# lp_pic32_s.net
KiCad netlist of a schematic drawn in EAGLE
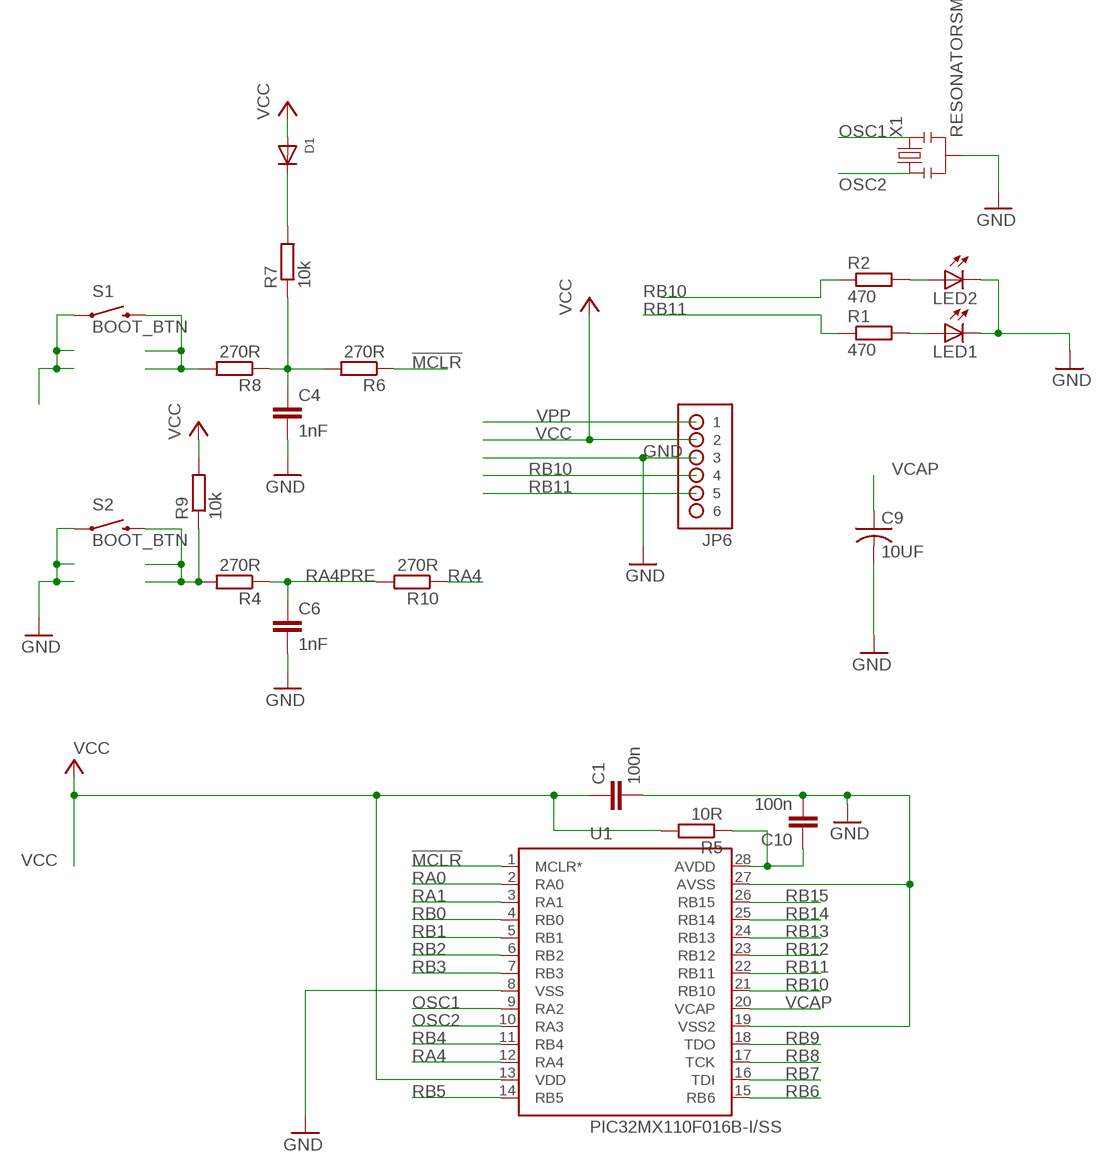
[diagram p0: schematic, sheet 1]

(export (version "E")
  (design (tool "Eeschema 10.0.6"))
  (components
    (comp (ref "C1")
      (value "100n")
      (footprint "eagle-import:C0805")
      (libsource (lib "eagle-import") (part "C-EUC0805"))
    )
    (comp (ref "C4")
      (value "1nF")
      (footprint "eagle-import:C0805")
      (libsource (lib "eagle-import") (part "resistor_C-EUC0805"))
    )
    (comp (ref "C6")
      (value "1nF")
      (footprint "eagle-import:C0805")
      (libsource (lib "eagle-import") (part "resistor_C-EUC0805"))
    )
    (comp (ref "C9")
      (value "10UF")
      (footprint "eagle-import:C1206")
      (libsource (lib "eagle-import") (part "C-USC1206"))
    )
    (comp (ref "C10")
      (value "100n")
      (footprint "eagle-import:C0805")
      (libsource (lib "eagle-import") (part "C-EUC0805"))
    )
    (comp (ref "D1")
      (value "DIODESOD-323F")
      (footprint "eagle-import:SOD-323F")
      (libsource (lib "eagle-import") (part "DIODESOD-323F"))
    )
    (comp (ref "JP6")
      (value "No Load")
      (footprint "eagle-import:HDR-1X6_OFFSET")
      (libsource (lib "eagle-import") (part "HDR-1X6-OFFSET"))
    )
    (comp (ref "LED1")
      (value "0")
      (footprint "eagle-import:CHIPLED_1206")
      (libsource (lib "eagle-import") (part "LEDCHIPLED_1206"))
    )
    (comp (ref "LED2")
      (value "0")
      (footprint "eagle-import:CHIPLED_1206")
      (libsource (lib "eagle-import") (part "LEDCHIPLED_1206"))
    )
    (comp (ref "R1")
      (value "470")
      (footprint "eagle-import:R0805")
      (libsource (lib "eagle-import") (part "R-EU_R0805"))
    )
    (comp (ref "R2")
      (value "470")
      (footprint "eagle-import:R0805")
      (libsource (lib "eagle-import") (part "R-EU_R0805"))
    )
    (comp (ref "R4")
      (value "270R")
      (footprint "eagle-import:R0805")
      (libsource (lib "eagle-import") (part "R-EU_R0805"))
    )
    (comp (ref "R5")
      (value "10R")
      (footprint "eagle-import:R0805")
      (libsource (lib "eagle-import") (part "R-EU_R0805"))
    )
    (comp (ref "R6")
      (value "270R")
      (footprint "eagle-import:R0805")
      (libsource (lib "eagle-import") (part "R-EU_R0805"))
    )
    (comp (ref "R7")
      (value "10k")
      (footprint "eagle-import:R0805")
      (libsource (lib "eagle-import") (part "R-EU_R0805"))
    )
    (comp (ref "R8")
      (value "270R")
      (footprint "eagle-import:R0805")
      (libsource (lib "eagle-import") (part "R-EU_R0805"))
    )
    (comp (ref "R9")
      (value "10k")
      (footprint "eagle-import:R0805")
      (libsource (lib "eagle-import") (part "R-EU_R0805"))
    )
    (comp (ref "R10")
      (value "270R")
      (footprint "eagle-import:R0805")
      (libsource (lib "eagle-import") (part "R-EU_R0805"))
    )
    (comp (ref "S1")
      (value "BOOT_BTN")
      (footprint "eagle-import:TACTILE-SWITCH-1101NE")
      (libsource (lib "eagle-import") (part "SWITCH-MOMENTARY-2-SMD-1101NE"))
    )
    (comp (ref "S2")
      (value "BOOT_BTN")
      (footprint "eagle-import:TACTILE-SWITCH-1101NE")
      (libsource (lib "eagle-import") (part "SWITCH-MOMENTARY-2-SMD-1101NE"))
    )
    (comp (ref "U1")
      (value "PIC32MX110F016B-I/SS")
      (footprint "eagle-import:SOP65P780X200-28N")
      (libsource (lib "eagle-import") (part "PIC32MX/SS110F016B-I"))
    )
    (comp (ref "X1")
      (value "RESONATORSMD")
      (footprint "eagle-import:RESONATOR-SMD")
      (libsource (lib "eagle-import") (part "RESONATORSMD"))
    )
  )
  (nets
    (net (code "1") (name "/OSC1") (class "Default")
      (node (ref "U1") (pin "9") (pinfunction "RA2_9") (pintype "bidirectional"))
      (node (ref "X1") (pin "3") (pinfunction "3_3") (pintype "passive"))
    )
    (net (code "2") (name "/OSC2") (class "Default")
      (node (ref "U1") (pin "10") (pinfunction "RA3_10") (pintype "bidirectional"))
      (node (ref "X1") (pin "1") (pinfunction "1_1") (pintype "passive"))
    )
    (net (code "3") (name "/RA0") (class "Default")
      (node (ref "U1") (pin "2") (pinfunction "RA0_2") (pintype "bidirectional"))
    )
    (net (code "4") (name "/RA1") (class "Default")
      (node (ref "U1") (pin "3") (pinfunction "RA1_3") (pintype "bidirectional"))
    )
    (net (code "5") (name "/RA4") (class "Default")
      (node (ref "R10") (pin "1") (pinfunction "1_1") (pintype "passive"))
      (node (ref "U1") (pin "12") (pinfunction "RA4_12") (pintype "bidirectional"))
    )
    (net (code "6") (name "/RA4PRE") (class "Default")
      (node (ref "C6") (pin "1") (pinfunction "1_1") (pintype "passive"))
      (node (ref "R10") (pin "2") (pinfunction "2_2") (pintype "passive"))
      (node (ref "R4") (pin "1") (pinfunction "1_1") (pintype "passive"))
    )
    (net (code "7") (name "/RB0") (class "Default")
      (node (ref "U1") (pin "4") (pinfunction "RB0_4") (pintype "bidirectional"))
    )
    (net (code "8") (name "/RB1") (class "Default")
      (node (ref "U1") (pin "5") (pinfunction "RB1_5") (pintype "bidirectional"))
    )
    (net (code "9") (name "/RB2") (class "Default")
      (node (ref "U1") (pin "6") (pinfunction "RB2_6") (pintype "bidirectional"))
    )
    (net (code "10") (name "/RB3") (class "Default")
      (node (ref "U1") (pin "7") (pinfunction "RB3_7") (pintype "bidirectional"))
    )
    (net (code "11") (name "/RB4") (class "Default")
      (node (ref "U1") (pin "11") (pinfunction "RB4_11") (pintype "bidirectional"))
    )
    (net (code "12") (name "/RB5") (class "Default")
      (node (ref "U1") (pin "14") (pinfunction "RB5_14") (pintype "bidirectional"))
    )
    (net (code "13") (name "/RB6") (class "Default")
      (node (ref "U1") (pin "15") (pinfunction "RB6_15") (pintype "bidirectional"))
    )
    (net (code "14") (name "/RB7") (class "Default")
      (node (ref "U1") (pin "16") (pinfunction "TDI_16") (pintype "input"))
    )
    (net (code "15") (name "/RB8") (class "Default")
      (node (ref "U1") (pin "17") (pinfunction "TCK_17") (pintype "input"))
    )
    (net (code "16") (name "/RB9") (class "Default")
      (node (ref "U1") (pin "18") (pinfunction "TDO_18") (pintype "output"))
    )
    (net (code "17") (name "/RB10") (class "Default")
      (node (ref "JP6") (pin "4") (pinfunction "4_4") (pintype "passive"))
      (node (ref "R2") (pin "1") (pinfunction "1_1") (pintype "passive"))
      (node (ref "U1") (pin "21") (pinfunction "RB10_21") (pintype "bidirectional"))
    )
    (net (code "18") (name "/RB11") (class "Default")
      (node (ref "JP6") (pin "5") (pinfunction "5_5") (pintype "passive"))
      (node (ref "R1") (pin "1") (pinfunction "1_1") (pintype "passive"))
      (node (ref "U1") (pin "22") (pinfunction "RB11_22") (pintype "bidirectional"))
    )
    (net (code "19") (name "/RB12") (class "Default")
      (node (ref "U1") (pin "23") (pinfunction "RB12_23") (pintype "bidirectional"))
    )
    (net (code "20") (name "/RB13") (class "Default")
      (node (ref "U1") (pin "24") (pinfunction "RB13_24") (pintype "bidirectional"))
    )
    (net (code "21") (name "/RB14") (class "Default")
      (node (ref "U1") (pin "25") (pinfunction "RB14_25") (pintype "bidirectional"))
    )
    (net (code "22") (name "/RB15") (class "Default")
      (node (ref "U1") (pin "26") (pinfunction "RB15_26") (pintype "bidirectional"))
    )
    (net (code "23") (name "/VCAP") (class "Default")
      (node (ref "C9") (pin "1") (pinfunction "1_1") (pintype "passive"))
      (node (ref "U1") (pin "20") (pinfunction "VCAP_20") (pintype "power_in"))
    )
    (net (code "24") (name "/VPP") (class "Default")
      (node (ref "C4") (pin "1") (pinfunction "1_1") (pintype "passive"))
      (node (ref "JP6") (pin "1") (pinfunction "1_1") (pintype "passive"))
      (node (ref "R6") (pin "2") (pinfunction "2_2") (pintype "passive"))
      (node (ref "R7") (pin "1") (pinfunction "1_1") (pintype "passive"))
      (node (ref "R8") (pin "1") (pinfunction "1_1") (pintype "passive"))
    )
    (net (code "25") (name "/~{MCLR}") (class "Default")
      (node (ref "R6") (pin "1") (pinfunction "1_1") (pintype "passive"))
      (node (ref "U1") (pin "1") (pinfunction "MCLR*_1") (pintype "input"))
    )
    (net (code "26") (name "GND") (class "Default")
      (node (ref "C1") (pin "2") (pinfunction "2_2") (pintype "passive"))
      (node (ref "C10") (pin "2") (pinfunction "2_2") (pintype "passive"))
      (node (ref "C4") (pin "2") (pinfunction "2_2") (pintype "passive"))
      (node (ref "C6") (pin "2") (pinfunction "2_2") (pintype "passive"))
      (node (ref "C9") (pin "2") (pinfunction "2_2") (pintype "passive"))
      (node (ref "JP6") (pin "3") (pinfunction "3_3") (pintype "passive"))
      (node (ref "LED1") (pin "C") (pinfunction "C_C") (pintype "passive"))
      (node (ref "LED2") (pin "C") (pinfunction "C_C") (pintype "passive"))
      (node (ref "S2") (pin "1") (pinfunction "1_1") (pintype "passive"))
      (node (ref "U1") (pin "19") (pinfunction "VSS2_19") (pintype "power_in"))
      (node (ref "U1") (pin "27") (pinfunction "AVSS_27") (pintype "power_in"))
      (node (ref "U1") (pin "8") (pinfunction "VSS_8") (pintype "power_in"))
      (node (ref "X1") (pin "2") (pinfunction "2_2") (pintype "passive"))
    )
    (net (code "27") (name "Net-(D1-PadC)") (class "Default")
      (node (ref "D1") (pin "C") (pinfunction "C_C") (pintype "passive"))
      (node (ref "R7") (pin "2") (pinfunction "2_2") (pintype "passive"))
    )
    (net (code "28") (name "Net-(LED1-PadA)") (class "Default")
      (node (ref "LED1") (pin "A") (pinfunction "A_A") (pintype "passive"))
      (node (ref "R1") (pin "2") (pinfunction "2_2") (pintype "passive"))
    )
    (net (code "29") (name "Net-(LED2-PadA)") (class "Default")
      (node (ref "LED2") (pin "A") (pinfunction "A_A") (pintype "passive"))
      (node (ref "R2") (pin "2") (pinfunction "2_2") (pintype "passive"))
    )
    (net (code "30") (name "Net-(R4-Pad2)") (class "Default")
      (node (ref "R4") (pin "2") (pinfunction "2_2") (pintype "passive"))
      (node (ref "R9") (pin "1") (pinfunction "1_1") (pintype "passive"))
      (node (ref "S2") (pin "2") (pinfunction "2_2") (pintype "passive"))
    )
    (net (code "31") (name "Net-(R8-Pad2)") (class "Default")
      (node (ref "R8") (pin "2") (pinfunction "2_2") (pintype "passive"))
      (node (ref "S1") (pin "2") (pinfunction "2_2") (pintype "passive"))
    )
    (net (code "32") (name "Net-(U1-AVDD)") (class "Default")
      (node (ref "C10") (pin "1") (pinfunction "1_1") (pintype "passive"))
      (node (ref "R5") (pin "1") (pinfunction "1_1") (pintype "passive"))
      (node (ref "U1") (pin "28") (pinfunction "AVDD_28") (pintype "power_in"))
    )
    (net (code "33") (name "VCC") (class "Default")
      (node (ref "C1") (pin "1") (pinfunction "1_1") (pintype "passive"))
      (node (ref "D1") (pin "A") (pinfunction "A_A") (pintype "passive"))
      (node (ref "JP6") (pin "2") (pinfunction "2_2") (pintype "passive"))
      (node (ref "R5") (pin "2") (pinfunction "2_2") (pintype "passive"))
      (node (ref "R9") (pin "2") (pinfunction "2_2") (pintype "passive"))
      (node (ref "U1") (pin "13") (pinfunction "VDD_13") (pintype "power_in"))
    )
    (net (code "34") (name "unconnected-(JP6-Pad6)") (class "Default")
      (node (ref "JP6") (pin "6") (pinfunction "6_6") (pintype "passive"))
    )
    (net (code "35") (name "unconnected-(S1-Pad1)") (class "Default")
      (node (ref "S1") (pin "1") (pinfunction "1_1") (pintype "passive"))
    )
  )
)
